# prize_delivery.net
KiCad netlist of a schematic drawn in EAGLE
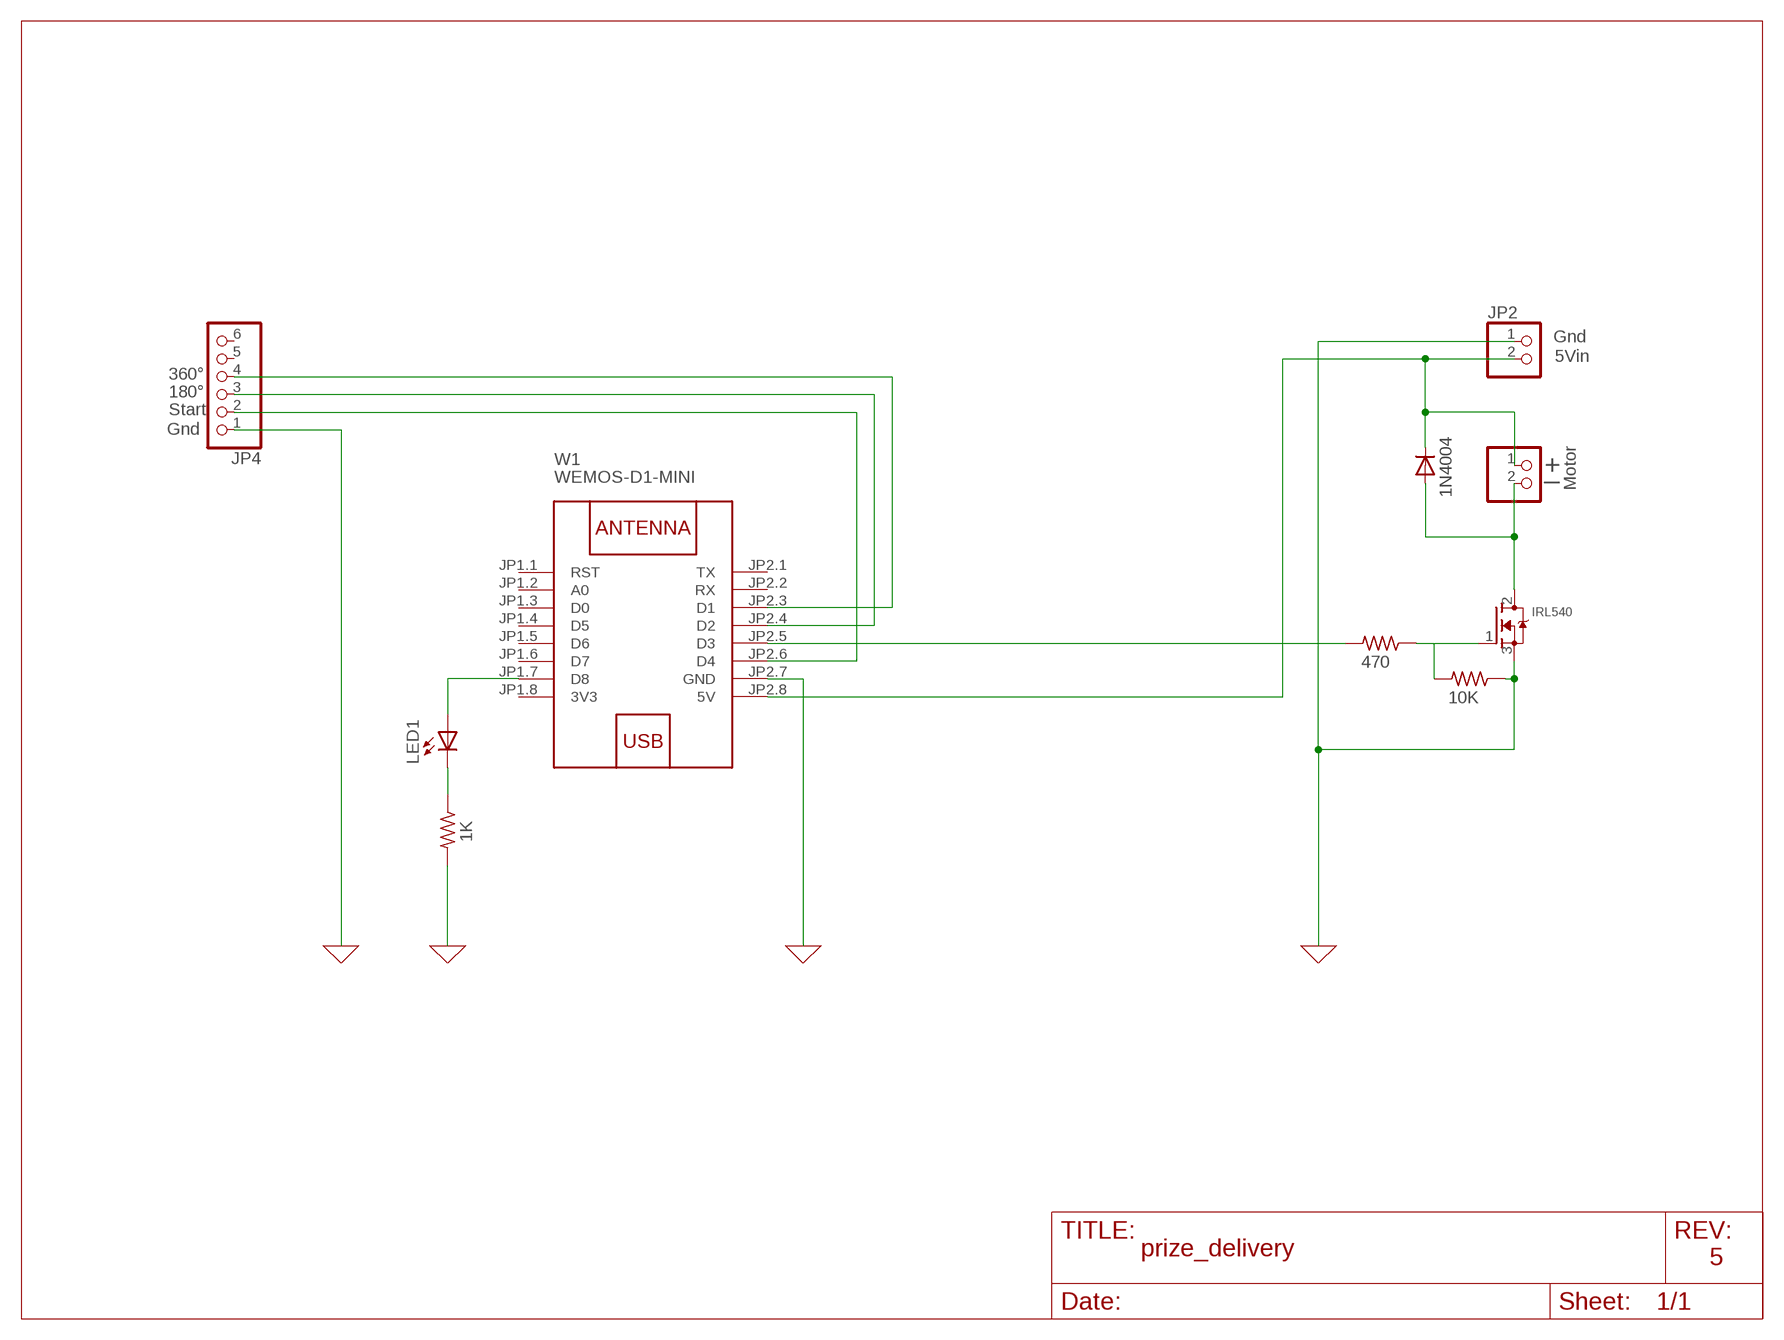
[diagram p0: schematic, sheet 1]

(export (version "E")
  (design (tool "Eeschema 10.0.6"))
  (components
    (comp (ref "D1")
      (value "1N4004")
      (footprint "eagle-import:DO41-10")
      (libsource (lib "eagle-import") (part "1N4004"))
    )
    (comp (ref "JP2")
      (value "5Vin")
      (footprint "eagle-import:1X02")
      (libsource (lib "eagle-import") (part "PINHD-1X2"))
    )
    (comp (ref "JP3")
      (value "Motor")
      (footprint "eagle-import:1X02")
      (libsource (lib "eagle-import") (part "PINHD-1X2"))
    )
    (comp (ref "JP4")
      (value "PINHD-1X6")
      (footprint "eagle-import:1X06")
      (libsource (lib "eagle-import") (part "PINHD-1X6"))
    )
    (comp (ref "LED1")
      (value "LED5MM")
      (footprint "eagle-import:LED5MM")
      (libsource (lib "eagle-import") (part "LED5MM"))
    )
    (comp (ref "Q1")
      (value "IRL540")
      (footprint "eagle-import:TO220V")
      (libsource (lib "eagle-import") (part "MOSFET-NGDS_TO220V"))
    )
    (comp (ref "R1")
      (value "1K")
      (footprint "eagle-import:0207_10")
      (libsource (lib "eagle-import") (part "R-US_0207/10"))
    )
    (comp (ref "R2")
      (value "470")
      (footprint "eagle-import:0207_10")
      (libsource (lib "eagle-import") (part "R-US_0207/10"))
    )
    (comp (ref "R4")
      (value "10K")
      (footprint "eagle-import:0207_10")
      (libsource (lib "eagle-import") (part "R-US_0207/10"))
    )
    (comp (ref "W1")
      (value "WEMOS-D1-MINI")
      (footprint "eagle-import:WEMOS-D1-MINI")
      (libsource (lib "eagle-import") (part "WEMOS-D1-MINI"))
    )
  )
  (nets
    (net (code "1") (name "/3V3") (class "Default")
      (node (ref "W1") (pin "JP1.8") (pinfunction "3V3_JP1.8") (pintype "power_in"))
    )
    (net (code "2") (name "GND") (class "Default")
      (node (ref "JP2") (pin "1") (pinfunction "1_1") (pintype "passive"))
      (node (ref "JP4") (pin "1") (pinfunction "1_1") (pintype "passive"))
      (node (ref "Q1") (pin "3") (pinfunction "S_3") (pintype "bidirectional"))
      (node (ref "R1") (pin "2") (pinfunction "2_2") (pintype "passive"))
      (node (ref "R4") (pin "1") (pinfunction "1_1") (pintype "passive"))
      (node (ref "W1") (pin "JP2.7") (pinfunction "GND_JP2.7") (pintype "power_in"))
    )
    (net (code "3") (name "Net-(LED1-C)") (class "Default")
      (node (ref "LED1") (pin "K") (pinfunction "C_K") (pintype "passive"))
      (node (ref "R1") (pin "1") (pinfunction "1_1") (pintype "passive"))
    )
    (net (code "4") (name "Net-(Q1-D)") (class "Default")
      (node (ref "D1") (pin "A") (pinfunction "A_A") (pintype "passive"))
      (node (ref "JP3") (pin "2") (pinfunction "2_2") (pintype "passive"))
      (node (ref "Q1") (pin "2") (pinfunction "D_2") (pintype "bidirectional"))
    )
    (net (code "5") (name "Net-(Q1-G)") (class "Default")
      (node (ref "Q1") (pin "1") (pinfunction "G_1") (pintype "bidirectional"))
      (node (ref "R2") (pin "1") (pinfunction "1_1") (pintype "passive"))
      (node (ref "R4") (pin "2") (pinfunction "2_2") (pintype "passive"))
    )
    (net (code "6") (name "Net-(W1-5V)") (class "Default")
      (node (ref "D1") (pin "C") (pinfunction "C_C") (pintype "passive"))
      (node (ref "JP2") (pin "2") (pinfunction "2_2") (pintype "passive"))
      (node (ref "JP3") (pin "1") (pinfunction "1_1") (pintype "passive"))
      (node (ref "W1") (pin "JP2.8") (pinfunction "5V_JP2.8") (pintype "power_in"))
    )
    (net (code "7") (name "Net-(W1-D1)") (class "Default")
      (node (ref "JP4") (pin "4") (pinfunction "4_4") (pintype "passive"))
      (node (ref "W1") (pin "JP2.3") (pinfunction "D1_JP2.3") (pintype "bidirectional"))
    )
    (net (code "8") (name "Net-(W1-D2)") (class "Default")
      (node (ref "JP4") (pin "3") (pinfunction "3_3") (pintype "passive"))
      (node (ref "W1") (pin "JP2.4") (pinfunction "D2_JP2.4") (pintype "bidirectional"))
    )
    (net (code "9") (name "Net-(W1-D3)") (class "Default")
      (node (ref "R2") (pin "2") (pinfunction "2_2") (pintype "passive"))
      (node (ref "W1") (pin "JP2.5") (pinfunction "D3_JP2.5") (pintype "bidirectional"))
    )
    (net (code "10") (name "Net-(W1-D4)") (class "Default")
      (node (ref "JP4") (pin "2") (pinfunction "2_2") (pintype "passive"))
      (node (ref "W1") (pin "JP2.6") (pinfunction "D4_JP2.6") (pintype "bidirectional"))
    )
    (net (code "11") (name "Net-(W1-D8)") (class "Default")
      (node (ref "LED1") (pin "A") (pinfunction "A_A") (pintype "passive"))
      (node (ref "W1") (pin "JP1.7") (pinfunction "D8_JP1.7") (pintype "bidirectional"))
    )
    (net (code "12") (name "unconnected-(JP4-Pad5)") (class "Default")
      (node (ref "JP4") (pin "5") (pinfunction "5_5") (pintype "passive"))
    )
    (net (code "13") (name "unconnected-(JP4-Pad6)") (class "Default")
      (node (ref "JP4") (pin "6") (pinfunction "6_6") (pintype "passive"))
    )
    (net (code "14") (name "unconnected-(W1-A0-PadJP1.2)") (class "Default")
      (node (ref "W1") (pin "JP1.2") (pinfunction "A0_JP1.2") (pintype "bidirectional"))
    )
    (net (code "15") (name "unconnected-(W1-D0-PadJP1.3)") (class "Default")
      (node (ref "W1") (pin "JP1.3") (pinfunction "D0_JP1.3") (pintype "bidirectional"))
    )
    (net (code "16") (name "unconnected-(W1-D5-PadJP1.4)") (class "Default")
      (node (ref "W1") (pin "JP1.4") (pinfunction "D5_JP1.4") (pintype "bidirectional"))
    )
    (net (code "17") (name "unconnected-(W1-D6-PadJP1.5)") (class "Default")
      (node (ref "W1") (pin "JP1.5") (pinfunction "D6_JP1.5") (pintype "bidirectional"))
    )
    (net (code "18") (name "unconnected-(W1-D7-PadJP1.6)") (class "Default")
      (node (ref "W1") (pin "JP1.6") (pinfunction "D7_JP1.6") (pintype "bidirectional"))
    )
    (net (code "19") (name "unconnected-(W1-RST-PadJP1.1)") (class "Default")
      (node (ref "W1") (pin "JP1.1") (pinfunction "RST_JP1.1") (pintype "bidirectional"))
    )
    (net (code "20") (name "unconnected-(W1-RX-PadJP2.2)") (class "Default")
      (node (ref "W1") (pin "JP2.2") (pinfunction "RX_JP2.2") (pintype "bidirectional"))
    )
    (net (code "21") (name "unconnected-(W1-TX-PadJP2.1)") (class "Default")
      (node (ref "W1") (pin "JP2.1") (pinfunction "TX_JP2.1") (pintype "bidirectional"))
    )
  )
)
